# Power_Distribution_-_DC-DC.net
KiCad netlist of a schematic drawn in Altium Designer
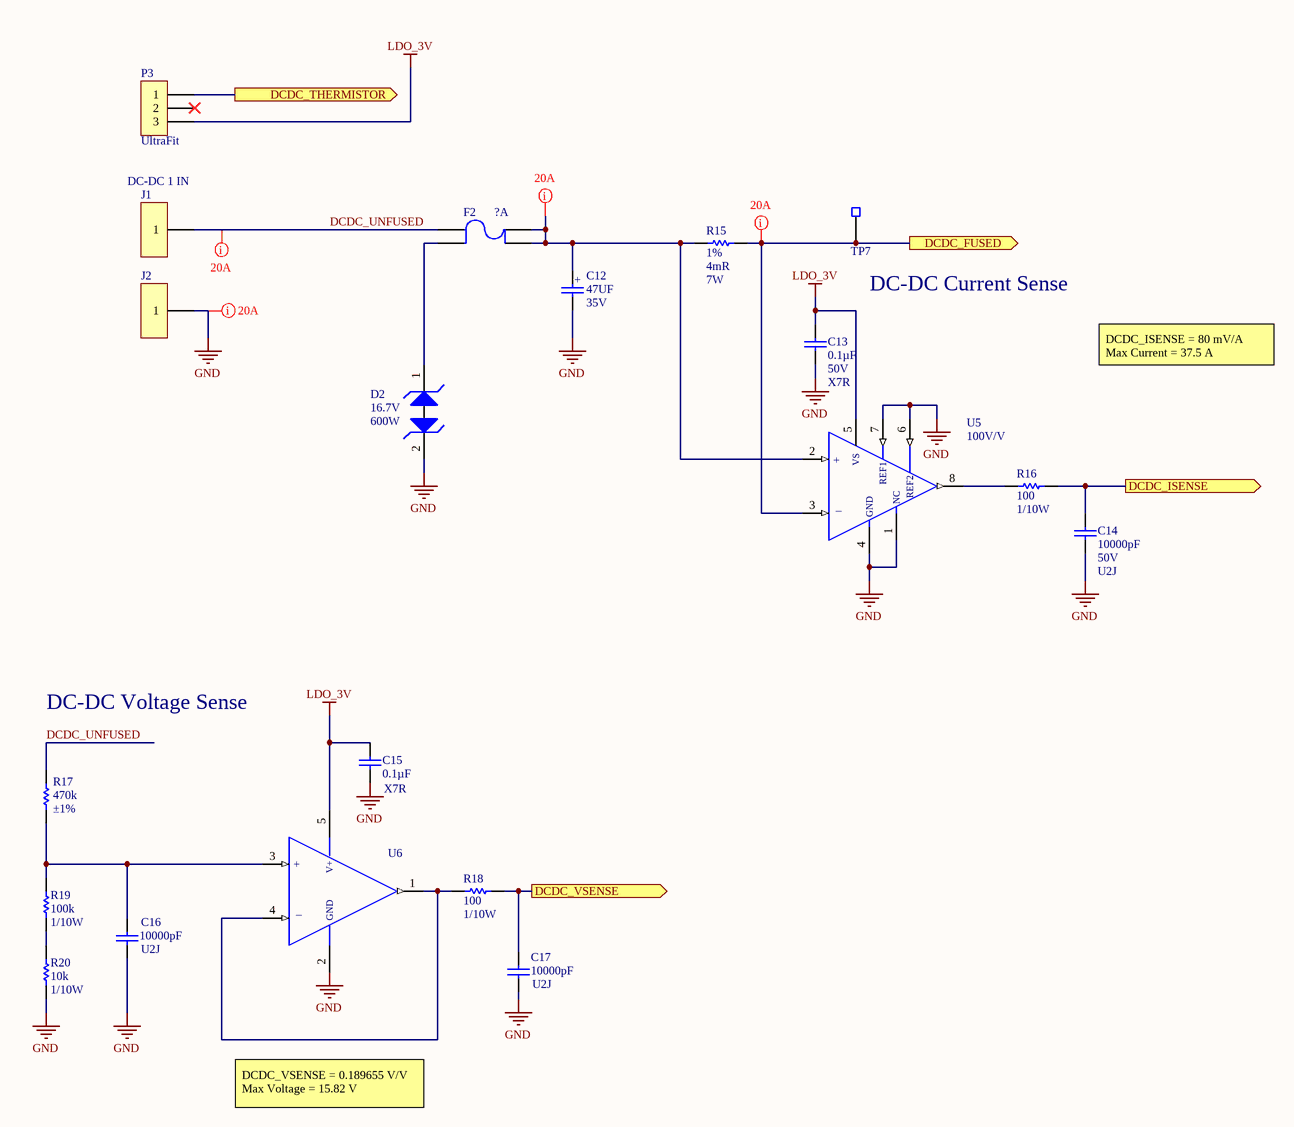
[diagram p0: Power Distribution - DC-DC.SchDoc]

(export (version "E")
  (design (tool "Eeschema 10.0.6"))
  (components
    (comp (ref "C12")
      (value "47UF")
      (footprint "CAP ALUM 6.3MM RADIAL SMD")
      (description "47µF 35V Aluminum Electrolytic Capacitors Radial, Can - SMD 1000 Hrs @ 85°C")
      (fields
        (field (name "MANUFACTURER") "Panasonic")
        (field (name "MANUFACTURER PART NUMBER") "EEE-1VA470WP")
        (field (name "VOLTAGE RATING") "35V")
      )
      (libsource (lib "Schematic Diagrams") (part "CAP ALUM 47UF 20% 35V SMD"))
    )
    (comp (ref "C13")
      (value "CAP CER 0.1UF 50V 10% X7R 0603")
      (footprint "CAP, 0603")
      (description "0.10µF ±10% 50V Ceramic Capacitor X7R 0603 (1608 Metric)")
      (fields
        (field (name "TOLERANCE") "±10%")
        (field (name "CAPACITANCE") "0.1µF")
        (field (name "VOLTAGE") "50V")
        (field (name "TEMPERATURE COEFFICIENT") "X7R")
      )
      (libsource (lib "Schematic Diagrams") (part "CAP CER 0.1UF 50V 10% X7R 0603"))
    )
    (comp (ref "C14")
      (value "CAP CER 10nF 50V 5% X7R 0603")
      (footprint "CAP, 0603")
      (description "10000pF ±5% 50V Ceramic Capacitor U2J 0603 (1608 Metric)")
      (fields
        (field (name "TOLERANCE") "±5%")
        (field (name "CAPACITANCE") "10000pF")
        (field (name "VOLTAGE") "50V")
        (field (name "TEMPERATURE COEFFICIENT") "U2J")
      )
      (libsource (lib "Schematic Diagrams") (part "CAP CER 10nF 50V 5% X7R 0603"))
    )
    (comp (ref "C15")
      (value "CAP CER 0.1UF 50V 10% X7R 0603")
      (footprint "CAP, 0603")
      (description "0.10µF ±10% 50V Ceramic Capacitor X7R 0603 (1608 Metric)")
      (fields
        (field (name "TOLERANCE") "±10%")
        (field (name "CAPACITANCE") "0.1µF")
        (field (name "TEMPERATURE COEFFICIENT") "X7R")
        (field (name "VOLTAGE") "50V")
      )
      (libsource (lib "Schematic Diagrams") (part "CAP CER 0.1UF 50V 10% X7R 0603"))
    )
    (comp (ref "C16")
      (value "CAP CER 10nF 50V 5% X7R 0603")
      (footprint "CAP, 0603")
      (description "10000pF ±5% 50V Ceramic Capacitor U2J 0603 (1608 Metric)")
      (fields
        (field (name "TOLERANCE") "±5%")
        (field (name "CAPACITANCE") "10000pF")
        (field (name "TEMPERATURE COEFFICIENT") "U2J")
        (field (name "VOLTAGE") "50V")
      )
      (libsource (lib "Schematic Diagrams") (part "CAP CER 10nF 50V 5% X7R 0603"))
    )
    (comp (ref "C17")
      (value "CAP CER 10nF 50V 5% X7R 0603")
      (footprint "CAP, 0603")
      (description "10000pF ±5% 50V Ceramic Capacitor U2J 0603 (1608 Metric)")
      (fields
        (field (name "TOLERANCE") "±5%")
        (field (name "CAPACITANCE") "10000pF")
        (field (name "TEMPERATURE COEFFICIENT") "U2J")
        (field (name "VOLTAGE") "50V")
      )
      (libsource (lib "Schematic Diagrams") (part "CAP CER 10nF 50V 5% X7R 0603"))
    )
    (comp (ref "D2")
      (value "DIODE TVS 15VWM 24.4VC DO-214AA (SMB)")
      (footprint "DO-214AA Diode")
      (description "TVS DIODE 15VWM 24.4VC SMB")
      (fields (field (name "VOLTAGE - BREAKDOWN (MIN)") "16.7V") (field (name "POWER - PEAK PULSE") "600W"))
      (libsource (lib "Schematic Diagrams") (part "DIODE TVS 15VWM 24.4VC DO-214AA (SMB)"))
    )
    (comp (ref "F2")
      (value "?A")
      (footprint "FUSE ATO/ATC FUSE HOLDER")
      (description "Fuse Block 30A 500V 1 Circuit Blade PCB")
      (fields (field (name "VOLTAGE") "500V"))
      (libsource (lib "Schematic Diagrams") (part "FUSE ATO FUSE HOLDER"))
    )
    (comp (ref "J1")
      (value "TERM PWR ELEMENT M8 25 PIN PCB")
      (footprint "TERM PWR ELEMENT M8 25 PIN PCB")
      (description "25 Pin Screw Terminal, Power Tap M8 Through Hole")
      (libsource (lib "Schematic Diagrams") (part "TERM PWR ELEMENT M8 25 PIN PCB"))
    )
    (comp (ref "J2")
      (value "TERM PWR ELEMENT M8 25 PIN PCB")
      (footprint "TERM PWR ELEMENT M8 25 PIN PCB")
      (description "25 Pin Screw Terminal, Power Tap M8 Through Hole")
      (libsource (lib "Schematic Diagrams") (part "TERM PWR ELEMENT M8 25 PIN PCB"))
    )
    (comp (ref "P3")
      (value "CONN 3POS ULTRA-FIT 0.138\"")
      (footprint "CONN, 3POS ULTRA-FIT")
      (description "3 Positions Header Connector 0.138\" (3.50mm) Through Hole Tin")
      (fields (field (name "VOLTAGE") "400V") (field (name "SERIES") "UltraFit"))
      (libsource (lib "Schematic Diagrams") (part "CONN 3POS ULTRA-FIT 0.138{dblquote}"))
    )
    (comp (ref "R15")
      (value "RES 0.004 OHM 1% 7W 5931")
      (footprint "RES 5931")
      (fields
        (field (name "TOLERANCE") "1%")
        (field (name "RESISTANCE") "4mR")
        (field (name "MAX POWER DISSIPATION") "7W")
      )
      (libsource (lib "Schematic Diagrams") (part "RES 0.004 OHM 1% 7W 5931"))
    )
    (comp (ref "R16")
      (value "RES 100 OHM 1% 1/10W 0603")
      (footprint "RES, 0603")
      (description "100 Ohm ±1% 0.1W, 1/10W Chip Resistor 0603 (1608 Metric) Moisture Resistant Thick Film")
      (fields
        (field (name "TOLERANCE") "±1%")
        (field (name "RESISTANCE") "100")
        (field (name "POWER") "1/10W")
      )
      (libsource (lib "Schematic Diagrams") (part "RES 100 OHM 1% 1/10W 0603"))
    )
    (comp (ref "R17")
      (value "RES 470K OHM 1% 1/4W 0603")
      (footprint "RES, 0603")
      (description "RES SMD 470K OHM 1% 1/4W 0603")
      (fields (field (name "RESISTANCE") "470k") (field (name "TOLERANCE") "±1%"))
      (libsource (lib "Schematic Diagrams") (part "RES 470K OHM 1% 1/4W 0603"))
    )
    (comp (ref "R18")
      (value "RES 100 OHM 1% 1/10W 0603")
      (footprint "RES, 0603")
      (description "100 Ohm ±1% 0.1W, 1/10W Chip Resistor 0603 (1608 Metric) Moisture Resistant Thick Film")
      (fields
        (field (name "TOLERANCE") "±1%")
        (field (name "RESISTANCE") "100")
        (field (name "POWER") "1/10W")
      )
      (libsource (lib "Schematic Diagrams") (part "RES 100 OHM 1% 1/10W 0603"))
    )
    (comp (ref "R19")
      (value "RES 100K OHM 5% 1/8W 0603")
      (footprint "RES, 0603")
      (description "RES SMD 100K OHM 5% 1/10W 0603")
      (fields
        (field (name "TOLERANCE") "±5%")
        (field (name "RESISTANCE") "100k")
        (field (name "POWER") "1/10W")
      )
      (libsource (lib "Schematic Diagrams") (part "RES 100K OHM 5% 1/8W 0603"))
    )
    (comp (ref "R20")
      (value "RES 10K OHM 1% 1/10W 0603")
      (footprint "RES, 0603")
      (description "RES SMD 10K OHM 1% 1/10W 0603")
      (fields
        (field (name "TOLERANCE") "±1%")
        (field (name "RESISTANCE") "10k")
        (field (name "POWER") "1/10W")
      )
      (libsource (lib "Schematic Diagrams") (part "RES 10K OHM 1% 1/10W 0603"))
    )
    (comp (ref "TP7")
      (value "Test Point 0603 SMD")
      (footprint "TEST POINT 0603 SMD")
      (libsource (lib "Schematic Diagrams") (part "Test Point 0603 SMD"))
    )
    (comp (ref "U5")
      (value "100V/V")
      (footprint "IC CURRENT AMPLIFIER INA240 TSSOP-8")
      (description "Current Sense Amplifier 1 Circuit 8-TSSOP")
      (libsource (lib "Schematic Diagrams") (part "IC CURRENT AMPLIFIER INA240 8-TSSOP"))
    )
    (comp (ref "U6")
      (value "IC OP AMP GEN PURPOSE RR 10MHZ SOT-23-5")
      (footprint "IC OP AMP GP RR 10MHZ SOT-23-5")
      (description "General Purpose Amplifier 1 Circuit Rail-to-Rail SOT-23-5")
      (libsource (lib "Schematic Diagrams") (part "IC OP AMP GEN PURPOSE RR 10MHZ SOT-23-5"))
    )
  )
  (nets
    (net (code "1") (name "/DCDC_FUSED") (class "Default")
      (node (ref "R15") (pin "2") (pinfunction "2_2") (pintype "passive"))
      (node (ref "TP7") (pin "1") (pinfunction "1_1") (pintype "passive"))
      (node (ref "U5") (pin "3") (pinfunction "-IN_3") (pintype "input"))
    )
    (net (code "2") (name "/DCDC_ISENSE") (class "Default")
      (node (ref "C14") (pin "1") (pinfunction "1_1") (pintype "passive"))
      (node (ref "R16") (pin "2") (pinfunction "2_2") (pintype "passive"))
    )
    (net (code "3") (name "/DCDC_THERMISTOR") (class "Default")
      (node (ref "P3") (pin "1") (pinfunction "1_1") (pintype "passive"))
    )
    (net (code "4") (name "/DCDC_UNFUSED") (class "Default")
      (node (ref "F2") (pin "1") (pinfunction "1_1") (pintype "passive"))
      (node (ref "J1") (pin "1") (pinfunction "1_1") (pintype "passive"))
      (node (ref "R17") (pin "1") (pinfunction "1_1") (pintype "passive"))
    )
    (net (code "5") (name "/DCDC_VSENSE") (class "Default")
      (node (ref "C17") (pin "1") (pinfunction "1_1") (pintype "passive"))
      (node (ref "R18") (pin "2") (pinfunction "2_2") (pintype "passive"))
    )
    (net (code "6") (name "GND") (class "Default")
      (node (ref "C12") (pin "2") (pinfunction "2_2") (pintype "passive"))
      (node (ref "C13") (pin "2") (pinfunction "2_2") (pintype "passive"))
      (node (ref "C14") (pin "2") (pinfunction "2_2") (pintype "passive"))
      (node (ref "C15") (pin "2") (pinfunction "2_2") (pintype "passive"))
      (node (ref "C16") (pin "2") (pinfunction "2_2") (pintype "passive"))
      (node (ref "C17") (pin "2") (pinfunction "2_2") (pintype "passive"))
      (node (ref "D2") (pin "2") (pinfunction "Cathode2_2") (pintype "passive"))
      (node (ref "J2") (pin "1") (pinfunction "1_1") (pintype "passive"))
      (node (ref "R20") (pin "2") (pinfunction "2_2") (pintype "passive"))
      (node (ref "U5") (pin "1") (pinfunction "NC_1") (pintype "power_in"))
      (node (ref "U5") (pin "4") (pinfunction "GND_4") (pintype "power_in"))
      (node (ref "U5") (pin "6") (pinfunction "REF2_6") (pintype "input"))
      (node (ref "U5") (pin "7") (pinfunction "REF1_7") (pintype "input"))
      (node (ref "U6") (pin "2") (pinfunction "VSS_2") (pintype "power_in"))
    )
    (net (code "7") (name "LDO_3V") (class "Default")
      (node (ref "C13") (pin "1") (pinfunction "1_1") (pintype "passive"))
      (node (ref "C15") (pin "1") (pinfunction "1_1") (pintype "passive"))
      (node (ref "P3") (pin "3") (pinfunction "3_3") (pintype "passive"))
      (node (ref "U5") (pin "5") (pinfunction "VS_5") (pintype "power_in"))
      (node (ref "U6") (pin "5") (pinfunction "VDD_5") (pintype "power_in"))
    )
    (net (code "8") (name "Net-(D2-Cathode1)") (class "Default")
      (node (ref "D2") (pin "1") (pinfunction "Cathode1_1") (pintype "passive"))
      (node (ref "F2") (pin "3") (pinfunction "3_3") (pintype "passive"))
    )
    (net (code "9") (name "Net-(R19-Pad2)") (class "Default")
      (node (ref "R19") (pin "2") (pinfunction "2_2") (pintype "passive"))
      (node (ref "R20") (pin "1") (pinfunction "1_1") (pintype "passive"))
    )
    (net (code "10") (name "Net-(U5-+IN)") (class "Default")
      (node (ref "C12") (pin "1") (pinfunction "1_1") (pintype "passive"))
      (node (ref "F2") (pin "2") (pinfunction "2_2") (pintype "passive"))
      (node (ref "F2") (pin "4") (pinfunction "4_4") (pintype "passive"))
      (node (ref "R15") (pin "1") (pinfunction "1_1") (pintype "passive"))
      (node (ref "U5") (pin "2") (pinfunction "+IN_2") (pintype "input"))
    )
    (net (code "11") (name "Net-(U5-OUTPUT)") (class "Default")
      (node (ref "R16") (pin "1") (pinfunction "1_1") (pintype "passive"))
      (node (ref "U5") (pin "8") (pinfunction "OUTPUT_8") (pintype "output"))
    )
    (net (code "12") (name "Net-(U6-+IN)") (class "Default")
      (node (ref "C16") (pin "1") (pinfunction "1_1") (pintype "passive"))
      (node (ref "R17") (pin "2") (pinfunction "2_2") (pintype "passive"))
      (node (ref "R19") (pin "1") (pinfunction "1_1") (pintype "passive"))
      (node (ref "U6") (pin "3") (pinfunction "+IN_3") (pintype "input"))
    )
    (net (code "13") (name "Net-(U6--IN)") (class "Default")
      (node (ref "R18") (pin "1") (pinfunction "1_1") (pintype "passive"))
      (node (ref "U6") (pin "1") (pinfunction "OUTPUT_1") (pintype "output"))
      (node (ref "U6") (pin "4") (pinfunction "-IN_4") (pintype "input"))
    )
    (net (code "14") (name "unconnected-(P3-Pad2)") (class "Default")
      (node (ref "P3") (pin "2") (pinfunction "2_2") (pintype "passive+no_connect"))
    )
  )
)
